# Current_Measurement.net
KiCad netlist of a schematic drawn in Altium Designer
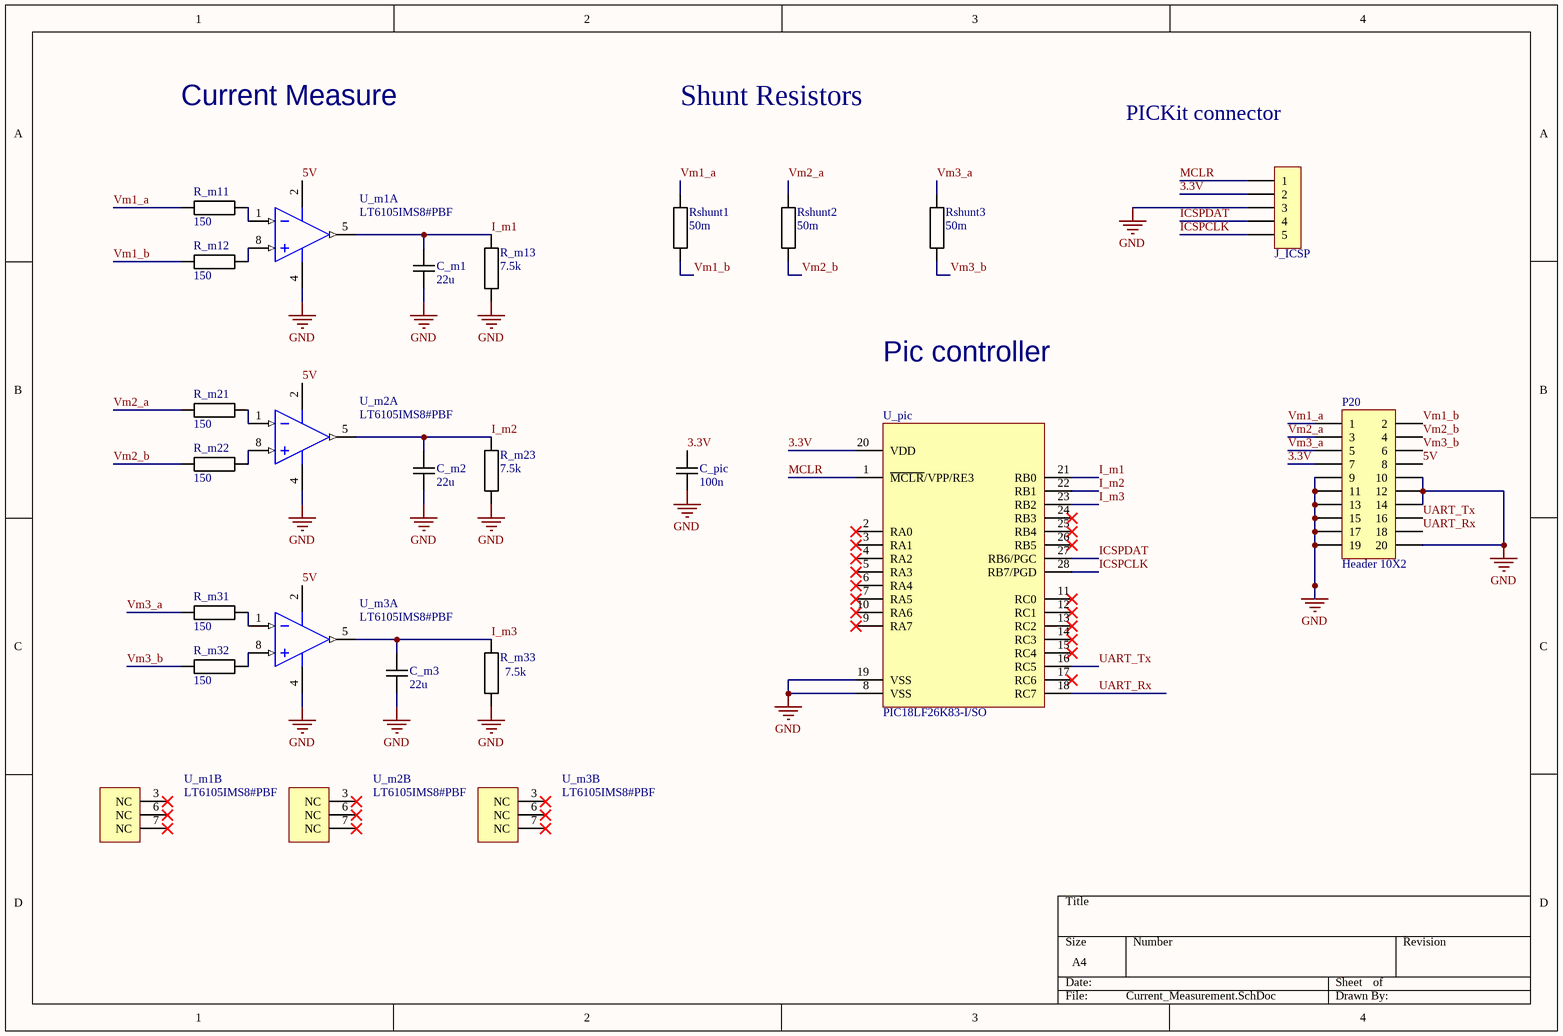
[diagram p0: Current_Measurement.SchDoc]

(export (version "E")
  (design (tool "Eeschema 10.0.6"))
  (components
    (comp (ref "C_m1")
      (value "22u")
      (footprint "RESC3115X65N")
      (description "Capacitor")
      (libsource (lib "Capacitor") (part "Capacitor"))
    )
    (comp (ref "C_m2")
      (value "22u")
      (footprint "RESC3115X65N")
      (description "Capacitor")
      (libsource (lib "Capacitor") (part "Capacitor"))
    )
    (comp (ref "C_m3")
      (value "22u")
      (footprint "RESC3115X65N")
      (description "Capacitor")
      (libsource (lib "Capacitor") (part "Capacitor"))
    )
    (comp (ref "C_pic")
      (value "100n")
      (footprint "RESC3115X65N")
      (description "Capacitor")
      (libsource (lib "Capacitor") (part "Capacitor"))
    )
    (comp (ref "J_ICSP")
      (value "*")
      (footprint "HDR1X5")
      (description "Plug connector")
      (libsource (lib "PinHeader") (part "PinHeader1x5"))
    )
    (comp (ref "P20")
      (value "Header 10X2")
      (footprint "HDR2X10")
      (description "Header, 10-Pin, Dual row")
      (fields (field (name "PUBLISHER") "Altium Limited"))
      (libsource (lib "Miscellaneous Connectors") (part "Header 10X2"))
    )
    (comp (ref "Rshunt1")
      (value "50m")
      (footprint "RESC3115X65N")
      (description "Resistor")
      (libsource (lib "Miscellaneous Devices") (part "Resistor"))
    )
    (comp (ref "Rshunt2")
      (value "50m")
      (footprint "RESC3115X65N")
      (description "Resistor")
      (libsource (lib "Resistor") (part "Resistor"))
    )
    (comp (ref "Rshunt3")
      (value "50m")
      (footprint "RESC3115X65N")
      (description "Resistor")
      (libsource (lib "Resistor") (part "Resistor"))
    )
    (comp (ref "R_m11")
      (value "150")
      (footprint "RESC3115X65N")
      (description "Resistor")
      (libsource (lib "Resistor") (part "Resistor"))
    )
    (comp (ref "R_m12")
      (value "150")
      (footprint "RESC3115X65N")
      (description "Resistor")
      (libsource (lib "Resistor") (part "Resistor"))
    )
    (comp (ref "R_m13")
      (value "7.5k")
      (footprint "RESC3115X65N")
      (description "Resistor")
      (libsource (lib "Resistor") (part "Resistor"))
    )
    (comp (ref "R_m21")
      (value "150")
      (footprint "RESC3115X65N")
      (description "Resistor")
      (libsource (lib "Resistor") (part "Resistor"))
    )
    (comp (ref "R_m22")
      (value "150")
      (footprint "RESC3115X65N")
      (description "Resistor")
      (libsource (lib "Resistor") (part "Resistor"))
    )
    (comp (ref "R_m23")
      (value "7.5k")
      (footprint "RESC3115X65N")
      (description "Resistor")
      (libsource (lib "Resistor") (part "Resistor"))
    )
    (comp (ref "R_m31")
      (value "150")
      (footprint "RESC3115X65N")
      (description "Resistor")
      (libsource (lib "Resistor") (part "Resistor"))
    )
    (comp (ref "R_m32")
      (value "150")
      (footprint "RESC3115X65N")
      (description "Resistor")
      (libsource (lib "Resistor") (part "Resistor"))
    )
    (comp (ref "R_m33")
      (value "7.5k")
      (footprint "RESC3115X65N")
      (description "Resistor")
      (libsource (lib "Resistor") (part "Resistor"))
    )
    (comp (ref "U_m1")
      (value "LT6105IMS8#PBF")
      (footprint "LT-MS8-8_L")
      (fields
        (field (name "LINEAR TECHNOLOGY PART NUMBER") "LT6105")
        (field (name "MANUFACTURER") "Linear Technology")
      )
      (libsource (lib "Linear_Technology_LT6105IMS8_PBF") (part "LT6105IMS8#PBF"))
    )
    (comp (ref "U_m2")
      (value "LT6105IMS8#PBF")
      (footprint "LT-MS8-8_L")
      (fields
        (field (name "LINEAR TECHNOLOGY PART NUMBER") "LT6105")
        (field (name "MANUFACTURER") "Linear Technology")
      )
      (libsource (lib "Linear_Technology_LT6105IMS8_PBF") (part "LT6105IMS8#PBF"))
    )
    (comp (ref "U_m3")
      (value "LT6105IMS8#PBF")
      (footprint "LT-MS8-8_N")
      (fields
        (field (name "LINEAR TECHNOLOGY PART NUMBER") "LT6105")
        (field (name "MANUFACTURER") "Linear Technology")
      )
      (libsource (lib "Linear_Technology_LT6105IMS8_PBF") (part "LT6105IMS8#PBF"))
    )
    (comp (ref "U_pic")
      (value "PIC18LF26K83-I/SO")
      (footprint "SOIC127P1030X265-28N")
      (description "Flash Microcontrollers  with 10-Bit A/D and nanoWatt Technology")
      (libsource (lib "Processor") (part "PIC18F26K83-_/SO"))
    )
  )
  (nets
    (net (code "1") (name "/3.3V") (class "Default")
      (node (ref "C_pic") (pin "2") (pinfunction "2_2") (pintype "passive"))
      (node (ref "J_ICSP") (pin "2") (pinfunction "2_2") (pintype "passive"))
      (node (ref "P20") (pin "7") (pinfunction "7_7") (pintype "passive"))
      (node (ref "U_pic") (pin "20") (pinfunction "VDD_20") (pintype "passive"))
    )
    (net (code "2") (name "/5V") (class "Default")
      (node (ref "P20") (pin "8") (pinfunction "8_8") (pintype "passive"))
      (node (ref "U_m1") (pin "2") (pinfunction "V+_2") (pintype "power_in"))
      (node (ref "U_m2") (pin "2") (pinfunction "V+_2") (pintype "power_in"))
      (node (ref "U_m3") (pin "2") (pinfunction "V+_2") (pintype "power_in"))
    )
    (net (code "3") (name "/ICSPCLK") (class "Default")
      (node (ref "J_ICSP") (pin "5") (pinfunction "5_5") (pintype "passive"))
      (node (ref "U_pic") (pin "28") (pinfunction "RB7/PGD_28") (pintype "passive"))
    )
    (net (code "4") (name "/ICSPDAT") (class "Default")
      (node (ref "J_ICSP") (pin "4") (pinfunction "4_4") (pintype "passive"))
      (node (ref "U_pic") (pin "27") (pinfunction "RB6/PGC_27") (pintype "passive"))
    )
    (net (code "5") (name "/I_m1") (class "Default")
      (node (ref "C_m1") (pin "2") (pinfunction "2_2") (pintype "passive"))
      (node (ref "R_m13") (pin "2") (pinfunction "2_2") (pintype "passive"))
      (node (ref "U_m1") (pin "5") (pinfunction "VOUT_5") (pintype "output"))
      (node (ref "U_pic") (pin "21") (pinfunction "RB0_21") (pintype "passive"))
    )
    (net (code "6") (name "/I_m2") (class "Default")
      (node (ref "C_m2") (pin "2") (pinfunction "2_2") (pintype "passive"))
      (node (ref "R_m23") (pin "2") (pinfunction "2_2") (pintype "passive"))
      (node (ref "U_m2") (pin "5") (pinfunction "VOUT_5") (pintype "output"))
      (node (ref "U_pic") (pin "22") (pinfunction "RB1_22") (pintype "passive"))
    )
    (net (code "7") (name "/I_m3") (class "Default")
      (node (ref "C_m3") (pin "2") (pinfunction "2_2") (pintype "passive"))
      (node (ref "R_m33") (pin "2") (pinfunction "2_2") (pintype "passive"))
      (node (ref "U_m3") (pin "5") (pinfunction "VOUT_5") (pintype "output"))
      (node (ref "U_pic") (pin "23") (pinfunction "RB2_23") (pintype "passive"))
    )
    (net (code "8") (name "/MCLR") (class "Default")
      (node (ref "J_ICSP") (pin "1") (pinfunction "1_1") (pintype "passive"))
      (node (ref "U_pic") (pin "1") (pinfunction "~{MCLR}/VPP/RE3_1") (pintype "passive"))
    )
    (net (code "9") (name "/UART_Rx") (class "Default")
      (node (ref "P20") (pin "18") (pinfunction "18_18") (pintype "passive"))
      (node (ref "U_pic") (pin "18") (pinfunction "RC7_18") (pintype "passive"))
    )
    (net (code "10") (name "/UART_Tx") (class "Default")
      (node (ref "P20") (pin "16") (pinfunction "16_16") (pintype "passive"))
      (node (ref "U_pic") (pin "16") (pinfunction "RC5_16") (pintype "passive"))
    )
    (net (code "11") (name "/Vm1_a") (class "Default")
      (node (ref "P20") (pin "1") (pinfunction "1_1") (pintype "passive"))
      (node (ref "R_m11") (pin "1") (pinfunction "1_1") (pintype "passive"))
      (node (ref "Rshunt1") (pin "2") (pinfunction "2_2") (pintype "passive"))
    )
    (net (code "12") (name "/Vm1_b") (class "Default")
      (node (ref "P20") (pin "2") (pinfunction "2_2") (pintype "passive"))
      (node (ref "R_m12") (pin "1") (pinfunction "1_1") (pintype "passive"))
      (node (ref "Rshunt1") (pin "1") (pinfunction "1_1") (pintype "passive"))
    )
    (net (code "13") (name "/Vm2_a") (class "Default")
      (node (ref "P20") (pin "3") (pinfunction "3_3") (pintype "passive"))
      (node (ref "R_m21") (pin "1") (pinfunction "1_1") (pintype "passive"))
      (node (ref "Rshunt2") (pin "2") (pinfunction "2_2") (pintype "passive"))
    )
    (net (code "14") (name "/Vm2_b") (class "Default")
      (node (ref "P20") (pin "4") (pinfunction "4_4") (pintype "passive"))
      (node (ref "R_m22") (pin "1") (pinfunction "1_1") (pintype "passive"))
      (node (ref "Rshunt2") (pin "1") (pinfunction "1_1") (pintype "passive"))
    )
    (net (code "15") (name "/Vm3_a") (class "Default")
      (node (ref "P20") (pin "5") (pinfunction "5_5") (pintype "passive"))
      (node (ref "R_m31") (pin "1") (pinfunction "1_1") (pintype "passive"))
      (node (ref "Rshunt3") (pin "2") (pinfunction "2_2") (pintype "passive"))
    )
    (net (code "16") (name "/Vm3_b") (class "Default")
      (node (ref "P20") (pin "6") (pinfunction "6_6") (pintype "passive"))
      (node (ref "R_m32") (pin "1") (pinfunction "1_1") (pintype "passive"))
      (node (ref "Rshunt3") (pin "1") (pinfunction "1_1") (pintype "passive"))
    )
    (net (code "17") (name "GND") (class "Default")
      (node (ref "C_m1") (pin "1") (pinfunction "1_1") (pintype "passive"))
      (node (ref "C_m2") (pin "1") (pinfunction "1_1") (pintype "passive"))
      (node (ref "C_m3") (pin "1") (pinfunction "1_1") (pintype "passive"))
      (node (ref "C_pic") (pin "1") (pinfunction "1_1") (pintype "passive"))
      (node (ref "J_ICSP") (pin "3") (pinfunction "3_3") (pintype "passive"))
      (node (ref "P20") (pin "10") (pinfunction "10_10") (pintype "passive"))
      (node (ref "P20") (pin "11") (pinfunction "11_11") (pintype "passive"))
      (node (ref "P20") (pin "12") (pinfunction "12_12") (pintype "passive"))
      (node (ref "P20") (pin "13") (pinfunction "13_13") (pintype "passive"))
      (node (ref "P20") (pin "14") (pinfunction "14_14") (pintype "passive"))
      (node (ref "P20") (pin "15") (pinfunction "15_15") (pintype "passive"))
      (node (ref "P20") (pin "17") (pinfunction "17_17") (pintype "passive"))
      (node (ref "P20") (pin "19") (pinfunction "19_19") (pintype "passive"))
      (node (ref "P20") (pin "20") (pinfunction "20_20") (pintype "passive"))
      (node (ref "P20") (pin "9") (pinfunction "9_9") (pintype "passive"))
      (node (ref "R_m13") (pin "1") (pinfunction "1_1") (pintype "passive"))
      (node (ref "R_m23") (pin "1") (pinfunction "1_1") (pintype "passive"))
      (node (ref "R_m33") (pin "1") (pinfunction "1_1") (pintype "passive"))
      (node (ref "U_m1") (pin "4") (pinfunction "V-_4") (pintype "power_in"))
      (node (ref "U_m2") (pin "4") (pinfunction "V-_4") (pintype "power_in"))
      (node (ref "U_m3") (pin "4") (pinfunction "V-_4") (pintype "power_in"))
      (node (ref "U_pic") (pin "19") (pinfunction "VSS_19") (pintype "passive"))
      (node (ref "U_pic") (pin "8") (pinfunction "VSS_8") (pintype "passive"))
    )
    (net (code "18") (name "Net-(U_m1A-+IN)") (class "Default")
      (node (ref "R_m12") (pin "2") (pinfunction "2_2") (pintype "passive"))
      (node (ref "U_m1") (pin "8") (pinfunction "+IN_8") (pintype "input"))
    )
    (net (code "19") (name "Net-(U_m1A--IN)") (class "Default")
      (node (ref "R_m11") (pin "2") (pinfunction "2_2") (pintype "passive"))
      (node (ref "U_m1") (pin "1") (pinfunction "-IN_1") (pintype "input"))
    )
    (net (code "20") (name "Net-(U_m2A-+IN)") (class "Default")
      (node (ref "R_m22") (pin "2") (pinfunction "2_2") (pintype "passive"))
      (node (ref "U_m2") (pin "8") (pinfunction "+IN_8") (pintype "input"))
    )
    (net (code "21") (name "Net-(U_m2A--IN)") (class "Default")
      (node (ref "R_m21") (pin "2") (pinfunction "2_2") (pintype "passive"))
      (node (ref "U_m2") (pin "1") (pinfunction "-IN_1") (pintype "input"))
    )
    (net (code "22") (name "Net-(U_m3A-+IN)") (class "Default")
      (node (ref "R_m32") (pin "2") (pinfunction "2_2") (pintype "passive"))
      (node (ref "U_m3") (pin "8") (pinfunction "+IN_8") (pintype "input"))
    )
    (net (code "23") (name "Net-(U_m3A--IN)") (class "Default")
      (node (ref "R_m31") (pin "2") (pinfunction "2_2") (pintype "passive"))
      (node (ref "U_m3") (pin "1") (pinfunction "-IN_1") (pintype "input"))
    )
    (net (code "24") (name "unconnected-(U_m1B-NC-Pad3)") (class "Default")
      (node (ref "U_m1") (pin "3") (pinfunction "NC_3") (pintype "passive+no_connect"))
    )
    (net (code "25") (name "unconnected-(U_m1B-NC-Pad6)") (class "Default")
      (node (ref "U_m1") (pin "6") (pinfunction "NC_6") (pintype "passive+no_connect"))
    )
    (net (code "26") (name "unconnected-(U_m1B-NC-Pad7)") (class "Default")
      (node (ref "U_m1") (pin "7") (pinfunction "NC_7") (pintype "passive+no_connect"))
    )
    (net (code "27") (name "unconnected-(U_m2B-NC-Pad3)") (class "Default")
      (node (ref "U_m2") (pin "3") (pinfunction "NC_3") (pintype "passive+no_connect"))
    )
    (net (code "28") (name "unconnected-(U_m2B-NC-Pad6)") (class "Default")
      (node (ref "U_m2") (pin "6") (pinfunction "NC_6") (pintype "passive+no_connect"))
    )
    (net (code "29") (name "unconnected-(U_m2B-NC-Pad7)") (class "Default")
      (node (ref "U_m2") (pin "7") (pinfunction "NC_7") (pintype "passive+no_connect"))
    )
    (net (code "30") (name "unconnected-(U_m3B-NC-Pad3)") (class "Default")
      (node (ref "U_m3") (pin "3") (pinfunction "NC_3") (pintype "passive+no_connect"))
    )
    (net (code "31") (name "unconnected-(U_m3B-NC-Pad6)") (class "Default")
      (node (ref "U_m3") (pin "6") (pinfunction "NC_6") (pintype "passive+no_connect"))
    )
    (net (code "32") (name "unconnected-(U_m3B-NC-Pad7)") (class "Default")
      (node (ref "U_m3") (pin "7") (pinfunction "NC_7") (pintype "passive+no_connect"))
    )
    (net (code "33") (name "unconnected-(U_pic-RA0-Pad2)") (class "Default")
      (node (ref "U_pic") (pin "2") (pinfunction "RA0_2") (pintype "passive+no_connect"))
    )
    (net (code "34") (name "unconnected-(U_pic-RA1-Pad3)") (class "Default")
      (node (ref "U_pic") (pin "3") (pinfunction "RA1_3") (pintype "passive+no_connect"))
    )
    (net (code "35") (name "unconnected-(U_pic-RA2-Pad4)") (class "Default")
      (node (ref "U_pic") (pin "4") (pinfunction "RA2_4") (pintype "passive+no_connect"))
    )
    (net (code "36") (name "unconnected-(U_pic-RA3-Pad5)") (class "Default")
      (node (ref "U_pic") (pin "5") (pinfunction "RA3_5") (pintype "passive+no_connect"))
    )
    (net (code "37") (name "unconnected-(U_pic-RA4-Pad6)") (class "Default")
      (node (ref "U_pic") (pin "6") (pinfunction "RA4_6") (pintype "passive+no_connect"))
    )
    (net (code "38") (name "unconnected-(U_pic-RA5-Pad7)") (class "Default")
      (node (ref "U_pic") (pin "7") (pinfunction "RA5_7") (pintype "passive+no_connect"))
    )
    (net (code "39") (name "unconnected-(U_pic-RA6-Pad10)") (class "Default")
      (node (ref "U_pic") (pin "10") (pinfunction "RA6_10") (pintype "passive+no_connect"))
    )
    (net (code "40") (name "unconnected-(U_pic-RA7-Pad9)") (class "Default")
      (node (ref "U_pic") (pin "9") (pinfunction "RA7_9") (pintype "passive+no_connect"))
    )
    (net (code "41") (name "unconnected-(U_pic-RB3-Pad24)") (class "Default")
      (node (ref "U_pic") (pin "24") (pinfunction "RB3_24") (pintype "passive+no_connect"))
    )
    (net (code "42") (name "unconnected-(U_pic-RB4-Pad25)") (class "Default")
      (node (ref "U_pic") (pin "25") (pinfunction "RB4_25") (pintype "passive+no_connect"))
    )
    (net (code "43") (name "unconnected-(U_pic-RB5-Pad26)") (class "Default")
      (node (ref "U_pic") (pin "26") (pinfunction "RB5_26") (pintype "passive+no_connect"))
    )
    (net (code "44") (name "unconnected-(U_pic-RC0-Pad11)") (class "Default")
      (node (ref "U_pic") (pin "11") (pinfunction "RC0_11") (pintype "passive+no_connect"))
    )
    (net (code "45") (name "unconnected-(U_pic-RC1-Pad12)") (class "Default")
      (node (ref "U_pic") (pin "12") (pinfunction "RC1_12") (pintype "passive+no_connect"))
    )
    (net (code "46") (name "unconnected-(U_pic-RC2-Pad13)") (class "Default")
      (node (ref "U_pic") (pin "13") (pinfunction "RC2_13") (pintype "passive+no_connect"))
    )
    (net (code "47") (name "unconnected-(U_pic-RC3-Pad14)") (class "Default")
      (node (ref "U_pic") (pin "14") (pinfunction "RC3_14") (pintype "passive+no_connect"))
    )
    (net (code "48") (name "unconnected-(U_pic-RC4-Pad15)") (class "Default")
      (node (ref "U_pic") (pin "15") (pinfunction "RC4_15") (pintype "passive+no_connect"))
    )
    (net (code "49") (name "unconnected-(U_pic-RC6-Pad17)") (class "Default")
      (node (ref "U_pic") (pin "17") (pinfunction "RC6_17") (pintype "passive+no_connect"))
    )
  )
)
